# AVR8_RedBoard.net
KiCad netlist of a schematic drawn in Altium Designer
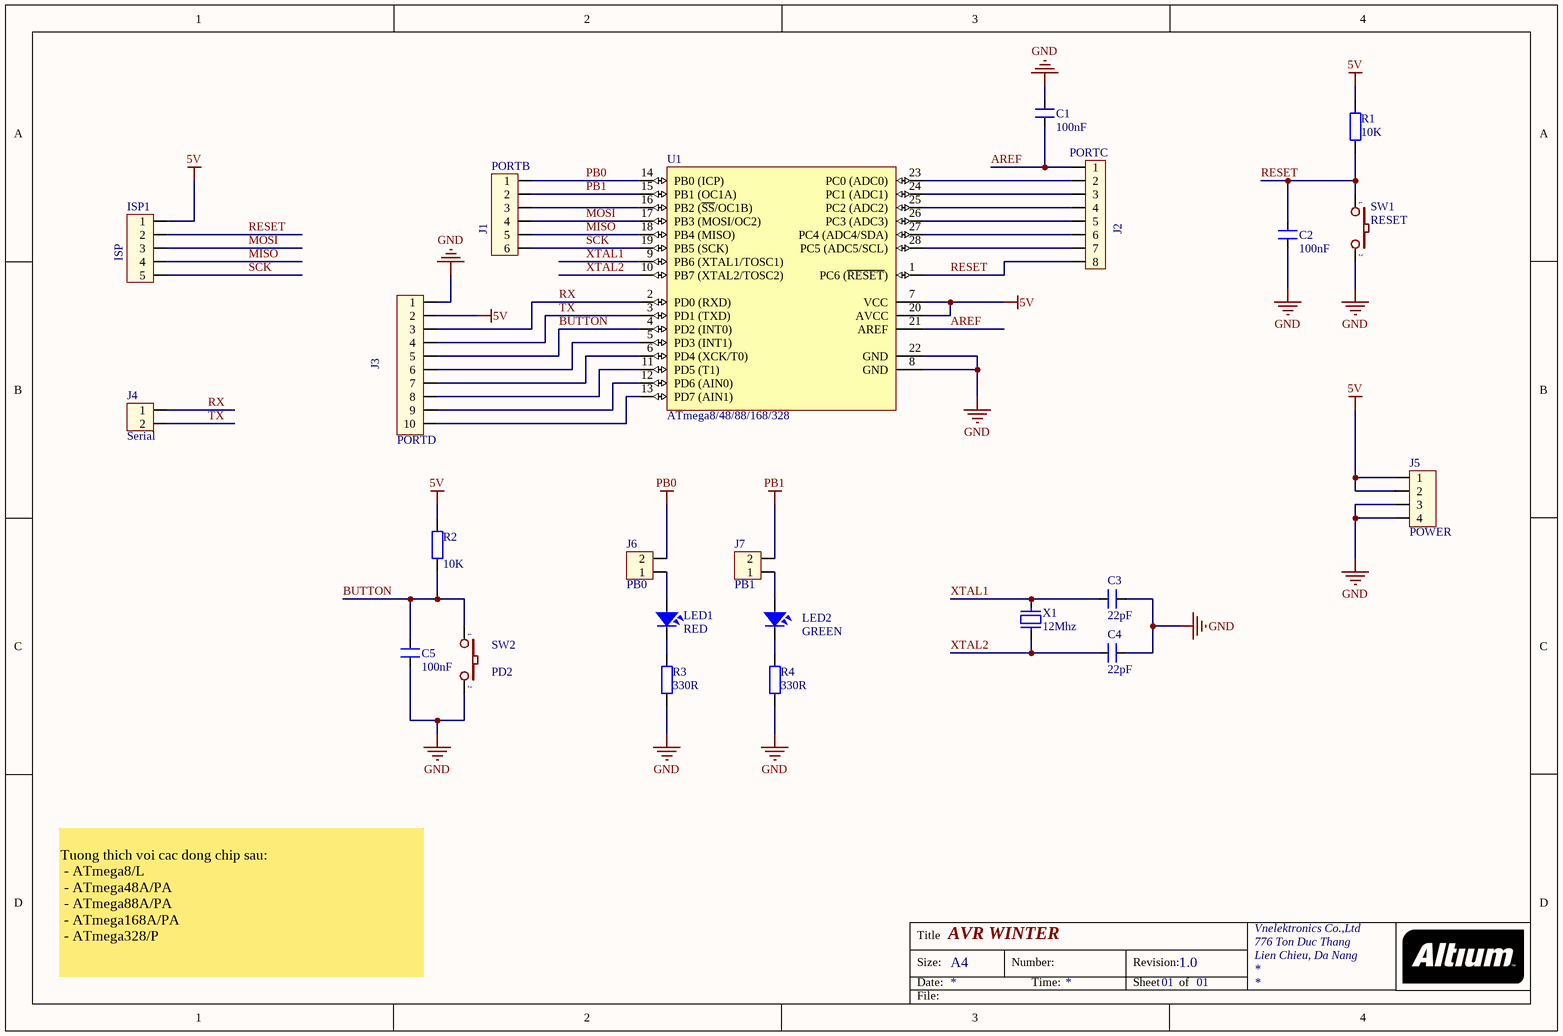
[diagram p0: AVR8 RedBoard.SchDoc]

(export (version "E")
  (design (tool "Eeschema 10.0.6"))
  (components
    (comp (ref "C1")
      (value "100nF")
      (footprint "C0805")
      (description "Cap np  1pF - 472pF")
      (libsource (lib "syhaunguyen") (part "CN1"))
    )
    (comp (ref "C2")
      (value "100nF")
      (footprint "C0805")
      (description "Cap np  1pF - 472pF")
      (libsource (lib "syhaunguyen") (part "CN1"))
    )
    (comp (ref "C3")
      (value "22pF")
      (footprint "C0603")
      (description "Cap np  1pF - 472pF")
      (libsource (lib "syhaunguyen") (part "CN1"))
    )
    (comp (ref "C4")
      (value "22pF")
      (footprint "C0603")
      (description "Cap np  1pF - 472pF")
      (libsource (lib "syhaunguyen") (part "CN1"))
    )
    (comp (ref "C5")
      (value "100nF")
      (footprint "C0805")
      (description "Cap np  1pF - 472pF")
      (libsource (lib "syhaunguyen") (part "CN1"))
    )
    (comp (ref "ISP1")
      (value "ISP")
      (footprint "Header_5")
      (description "Header 5 (Green)")
      (libsource (lib "Tran Tuan") (part "Hed5"))
    )
    (comp (ref "J1")
      (value "PORTB")
      (footprint "Header_6")
      (description "Header 6")
      (libsource (lib "Tran Tuan") (part "Hed6"))
    )
    (comp (ref "J2")
      (value "PORTC")
      (footprint "Header_8")
      (description "Hedear 8")
      (fields (field (name "CREAT BY") "VanDungEvn@Gmail.com"))
      (libsource (lib "syhaunguyen") (part "Hed8"))
    )
    (comp (ref "J3")
      (value "PORTD")
      (footprint "Header_10")
      (description "Header 10")
      (libsource (lib "Tran Tuan") (part "Hed10"))
    )
    (comp (ref "J4")
      (value "Serial")
      (footprint "Header_2")
      (description "Header 2 (Green)")
      (libsource (lib "") (part "Hed2_1"))
    )
    (comp (ref "J5")
      (value "POWER")
      (footprint "Header_4")
      (description "Header 4 (Green)")
      (libsource (lib "VNELEK") (part "Hed4"))
    )
    (comp (ref "J6")
      (value "PB0")
      (footprint "Header_2")
      (description "Header 2 (Green)")
      (libsource (lib "syhaunguyen") (part "Hed2"))
    )
    (comp (ref "J7")
      (value "PB1")
      (footprint "Header_2")
      (description "Header 2 (Green)")
      (libsource (lib "syhaunguyen") (part "Hed2"))
    )
    (comp (ref "LED1")
      (value "RED")
      (footprint "Led 0805R")
      (description "LED Single colour Green and Red")
      (libsource (lib "syhaunguyen") (part "LED"))
    )
    (comp (ref "LED2")
      (value "GREEN")
      (footprint "Led 0805G")
      (description "LED Single colour Green and Red")
      (libsource (lib "syhaunguyen") (part "LED"))
    )
    (comp (ref "R1")
      (value "10K")
      (footprint "RESC2012(0805)")
      (description "Resistor")
      (fields (field (name "Comment") "Res2") (field (name "PUBLISHER") "Altium Limited"))
      (libsource (lib "") (part "Res2_1"))
    )
    (comp (ref "R2")
      (value "10K")
      (footprint "RESC2012(0805)")
      (description "Resistor")
      (fields (field (name "Comment") "Res2") (field (name "PUBLISHER") "Altium Limited"))
      (libsource (lib "") (part "Res2_1"))
    )
    (comp (ref "R3")
      (value "330R")
      (footprint "RESC2012(0805)")
      (description "Resistor")
      (fields (field (name "Comment") "Res2") (field (name "PUBLISHER") "Altium Limited"))
      (libsource (lib "Miscellaneous Devices") (part "Res2"))
    )
    (comp (ref "R4")
      (value "330R")
      (footprint "RESC2012(0805)")
      (description "Resistor")
      (fields (field (name "Comment") "Res2") (field (name "PUBLISHER") "Altium Limited"))
      (libsource (lib "Miscellaneous Devices") (part "Res2"))
    )
    (comp (ref "SW1")
      (value "RESET")
      (footprint "BUTTON 2PIN TRON")
      (description "Switch button 2 pin")
      (libsource (lib "VNELEK") (part "SW2"))
    )
    (comp (ref "SW2")
      (value "PD2")
      (footprint "BUTTON 2PIN TRON")
      (description "Switch button 2 pin")
      (libsource (lib "VNELEK") (part "SW2"))
    )
    (comp (ref "U1")
      (value "ATmega8/48/88/168/328")
      (footprint "SOCKET_28")
      (description "8-Bit AVR Microcontroller with 8K Bytes of In-System Programmable Flash Memory")
      (libsource (lib "syhaunguyen") (part "ATmega8-L"))
    )
    (comp (ref "X1")
      (value "12Mhz")
      (footprint "CRYSTAL")
      (description "Crystal For all Crystal 2pin.")
      (libsource (lib "syhaunguyen") (part "XT2"))
    )
  )
  (nets
    (net (code "1") (name "/AREF") (class "Default")
      (node (ref "C1") (pin "2") (pinfunction "2_2") (pintype "passive"))
      (node (ref "J2") (pin "1") (pinfunction "1_1") (pintype "passive"))
      (node (ref "U1") (pin "21") (pinfunction "AREF_21") (pintype "passive"))
    )
    (net (code "2") (name "/BUTTON") (class "Default")
      (node (ref "C5") (pin "1") (pinfunction "1_1") (pintype "passive"))
      (node (ref "J3") (pin "5") (pinfunction "5_5") (pintype "passive"))
      (node (ref "R2") (pin "1") (pinfunction "1_1") (pintype "passive"))
      (node (ref "SW2") (pin "1") (pinfunction "1_1") (pintype "passive"))
      (node (ref "U1") (pin "4") (pinfunction "PD2_(INT0)_4") (pintype "bidirectional"))
    )
    (net (code "3") (name "/MISO") (class "Default")
      (node (ref "ISP1") (pin "4") (pinfunction "4_4") (pintype "passive"))
      (node (ref "J1") (pin "5") (pinfunction "5_5") (pintype "passive"))
      (node (ref "U1") (pin "18") (pinfunction "PB4_(MISO)_18") (pintype "bidirectional"))
    )
    (net (code "4") (name "/MOSI") (class "Default")
      (node (ref "ISP1") (pin "3") (pinfunction "3_3") (pintype "passive"))
      (node (ref "J1") (pin "4") (pinfunction "4_4") (pintype "passive"))
      (node (ref "U1") (pin "17") (pinfunction "PB3_(MOSI/OC2)_17") (pintype "bidirectional"))
    )
    (net (code "5") (name "/RESET") (class "Default")
      (node (ref "C2") (pin "1") (pinfunction "1_1") (pintype "passive"))
      (node (ref "ISP1") (pin "2") (pinfunction "2_2") (pintype "passive"))
      (node (ref "J2") (pin "8") (pinfunction "8_8") (pintype "passive"))
      (node (ref "R1") (pin "1") (pinfunction "1_1") (pintype "passive"))
      (node (ref "SW1") (pin "1") (pinfunction "1_1") (pintype "passive"))
      (node (ref "U1") (pin "1") (pinfunction "PC6_(~{RESET})_1") (pintype "bidirectional"))
    )
    (net (code "6") (name "/RX") (class "Default")
      (node (ref "J3") (pin "3") (pinfunction "3_3") (pintype "passive"))
      (node (ref "J4") (pin "1") (pinfunction "1_1") (pintype "passive"))
      (node (ref "U1") (pin "2") (pinfunction "PD0_(RXD)_2") (pintype "bidirectional"))
    )
    (net (code "7") (name "/SCK") (class "Default")
      (node (ref "ISP1") (pin "5") (pinfunction "5_5") (pintype "passive"))
      (node (ref "J1") (pin "6") (pinfunction "6_6") (pintype "passive"))
      (node (ref "U1") (pin "19") (pinfunction "PB5_(SCK)_19") (pintype "bidirectional"))
    )
    (net (code "8") (name "/TX") (class "Default")
      (node (ref "J3") (pin "4") (pinfunction "4_4") (pintype "passive"))
      (node (ref "J4") (pin "2") (pinfunction "2_2") (pintype "passive"))
      (node (ref "U1") (pin "3") (pinfunction "PD1_(TXD)_3") (pintype "bidirectional"))
    )
    (net (code "9") (name "/XTAL1") (class "Default")
      (node (ref "C3") (pin "2") (pinfunction "2_2") (pintype "passive"))
      (node (ref "U1") (pin "9") (pinfunction "PB6_(XTAL1/TOSC1)_9") (pintype "bidirectional"))
      (node (ref "X1") (pin "1") (pinfunction "1_1") (pintype "passive"))
    )
    (net (code "10") (name "/XTAL2") (class "Default")
      (node (ref "C4") (pin "2") (pinfunction "2_2") (pintype "passive"))
      (node (ref "U1") (pin "10") (pinfunction "PB7_(XTAL2/TOSC2)_10") (pintype "bidirectional"))
      (node (ref "X1") (pin "2") (pinfunction "2_2") (pintype "passive"))
    )
    (net (code "11") (name "5V") (class "Default")
      (node (ref "ISP1") (pin "1") (pinfunction "1_1") (pintype "passive"))
      (node (ref "J3") (pin "2") (pinfunction "2_2") (pintype "passive"))
      (node (ref "J5") (pin "1") (pinfunction "1_1") (pintype "passive"))
      (node (ref "J5") (pin "2") (pinfunction "2_2") (pintype "passive"))
      (node (ref "R1") (pin "2") (pinfunction "2_2") (pintype "passive"))
      (node (ref "R2") (pin "2") (pinfunction "2_2") (pintype "passive"))
      (node (ref "U1") (pin "20") (pinfunction "AVCC_20") (pintype "power_in"))
      (node (ref "U1") (pin "7") (pinfunction "VCC_7") (pintype "power_in"))
    )
    (net (code "12") (name "GND") (class "Default")
      (node (ref "C1") (pin "1") (pinfunction "1_1") (pintype "passive"))
      (node (ref "C2") (pin "2") (pinfunction "2_2") (pintype "passive"))
      (node (ref "C3") (pin "1") (pinfunction "1_1") (pintype "passive"))
      (node (ref "C4") (pin "1") (pinfunction "1_1") (pintype "passive"))
      (node (ref "C5") (pin "2") (pinfunction "2_2") (pintype "passive"))
      (node (ref "J3") (pin "1") (pinfunction "1_1") (pintype "passive"))
      (node (ref "J5") (pin "3") (pinfunction "3_3") (pintype "passive"))
      (node (ref "J5") (pin "4") (pinfunction "4_4") (pintype "passive"))
      (node (ref "R3") (pin "2") (pinfunction "2_2") (pintype "passive"))
      (node (ref "R4") (pin "2") (pinfunction "2_2") (pintype "passive"))
      (node (ref "SW1") (pin "2") (pinfunction "2_2") (pintype "passive"))
      (node (ref "SW2") (pin "2") (pinfunction "2_2") (pintype "passive"))
      (node (ref "U1") (pin "22") (pinfunction "GND_22") (pintype "power_in"))
      (node (ref "U1") (pin "8") (pinfunction "GND_8") (pintype "power_in"))
    )
    (net (code "13") (name "Net-(J6-Pad1)") (class "Default")
      (node (ref "J6") (pin "1") (pinfunction "1_1") (pintype "passive"))
      (node (ref "LED1") (pin "1") (pinfunction "1_1") (pintype "passive"))
    )
    (net (code "14") (name "Net-(J7-Pad1)") (class "Default")
      (node (ref "J7") (pin "1") (pinfunction "1_1") (pintype "passive"))
      (node (ref "LED2") (pin "1") (pinfunction "1_1") (pintype "passive"))
    )
    (net (code "15") (name "Net-(LED1-Pad2)") (class "Default")
      (node (ref "LED1") (pin "2") (pinfunction "2_2") (pintype "passive"))
      (node (ref "R3") (pin "1") (pinfunction "1_1") (pintype "passive"))
    )
    (net (code "16") (name "Net-(LED2-Pad2)") (class "Default")
      (node (ref "LED2") (pin "2") (pinfunction "2_2") (pintype "passive"))
      (node (ref "R4") (pin "1") (pinfunction "1_1") (pintype "passive"))
    )
    (net (code "17") (name "Net-(U1-PB2_(~{SS}{slash}OC1B))") (class "Default")
      (node (ref "J1") (pin "3") (pinfunction "3_3") (pintype "passive"))
      (node (ref "U1") (pin "16") (pinfunction "PB2_(~{SS}/OC1B)_16") (pintype "bidirectional"))
    )
    (net (code "18") (name "Net-(U1-PC0_(ADC0))") (class "Default")
      (node (ref "J2") (pin "2") (pinfunction "2_2") (pintype "passive"))
      (node (ref "U1") (pin "23") (pinfunction "PC0_(ADC0)_23") (pintype "bidirectional"))
    )
    (net (code "19") (name "Net-(U1-PC1_(ADC1))") (class "Default")
      (node (ref "J2") (pin "3") (pinfunction "3_3") (pintype "passive"))
      (node (ref "U1") (pin "24") (pinfunction "PC1_(ADC1)_24") (pintype "bidirectional"))
    )
    (net (code "20") (name "Net-(U1-PC2_(ADC2))") (class "Default")
      (node (ref "J2") (pin "4") (pinfunction "4_4") (pintype "passive"))
      (node (ref "U1") (pin "25") (pinfunction "PC2_(ADC2)_25") (pintype "bidirectional"))
    )
    (net (code "21") (name "Net-(U1-PC3_(ADC3))") (class "Default")
      (node (ref "J2") (pin "5") (pinfunction "5_5") (pintype "passive"))
      (node (ref "U1") (pin "26") (pinfunction "PC3_(ADC3)_26") (pintype "bidirectional"))
    )
    (net (code "22") (name "Net-(U1-PC4_(ADC4{slash}SDA))") (class "Default")
      (node (ref "J2") (pin "6") (pinfunction "6_6") (pintype "passive"))
      (node (ref "U1") (pin "27") (pinfunction "PC4_(ADC4/SDA)_27") (pintype "bidirectional"))
    )
    (net (code "23") (name "Net-(U1-PC5_(ADC5{slash}SCL))") (class "Default")
      (node (ref "J2") (pin "7") (pinfunction "7_7") (pintype "passive"))
      (node (ref "U1") (pin "28") (pinfunction "PC5_(ADC5/SCL)_28") (pintype "bidirectional"))
    )
    (net (code "24") (name "Net-(U1-PD3_(INT1))") (class "Default")
      (node (ref "J3") (pin "6") (pinfunction "6_6") (pintype "passive"))
      (node (ref "U1") (pin "5") (pinfunction "PD3_(INT1)_5") (pintype "bidirectional"))
    )
    (net (code "25") (name "Net-(U1-PD4_(XCK{slash}T0))") (class "Default")
      (node (ref "J3") (pin "7") (pinfunction "7_7") (pintype "passive"))
      (node (ref "U1") (pin "6") (pinfunction "PD4_(XCK/T0)_6") (pintype "bidirectional"))
    )
    (net (code "26") (name "Net-(U1-PD5_(T1))") (class "Default")
      (node (ref "J3") (pin "8") (pinfunction "8_8") (pintype "passive"))
      (node (ref "U1") (pin "11") (pinfunction "PD5_(T1)_11") (pintype "bidirectional"))
    )
    (net (code "27") (name "Net-(U1-PD6_(AIN0))") (class "Default")
      (node (ref "J3") (pin "9") (pinfunction "9_9") (pintype "passive"))
      (node (ref "U1") (pin "12") (pinfunction "PD6_(AIN0)_12") (pintype "bidirectional"))
    )
    (net (code "28") (name "Net-(U1-PD7_(AIN1))") (class "Default")
      (node (ref "J3") (pin "10") (pinfunction "10_10") (pintype "passive"))
      (node (ref "U1") (pin "13") (pinfunction "PD7_(AIN1)_13") (pintype "bidirectional"))
    )
    (net (code "29") (name "PB0") (class "Default")
      (node (ref "J1") (pin "1") (pinfunction "1_1") (pintype "passive"))
      (node (ref "J6") (pin "2") (pinfunction "2_2") (pintype "passive"))
      (node (ref "U1") (pin "14") (pinfunction "PB0_(ICP)_14") (pintype "bidirectional"))
    )
    (net (code "30") (name "PB1") (class "Default")
      (node (ref "J1") (pin "2") (pinfunction "2_2") (pintype "passive"))
      (node (ref "J7") (pin "2") (pinfunction "2_2") (pintype "passive"))
      (node (ref "U1") (pin "15") (pinfunction "PB1_(OC1A)_15") (pintype "bidirectional"))
    )
  )
)
